# vco-4069-schmitz.net
KiCad netlist of a schematic drawn in EAGLE
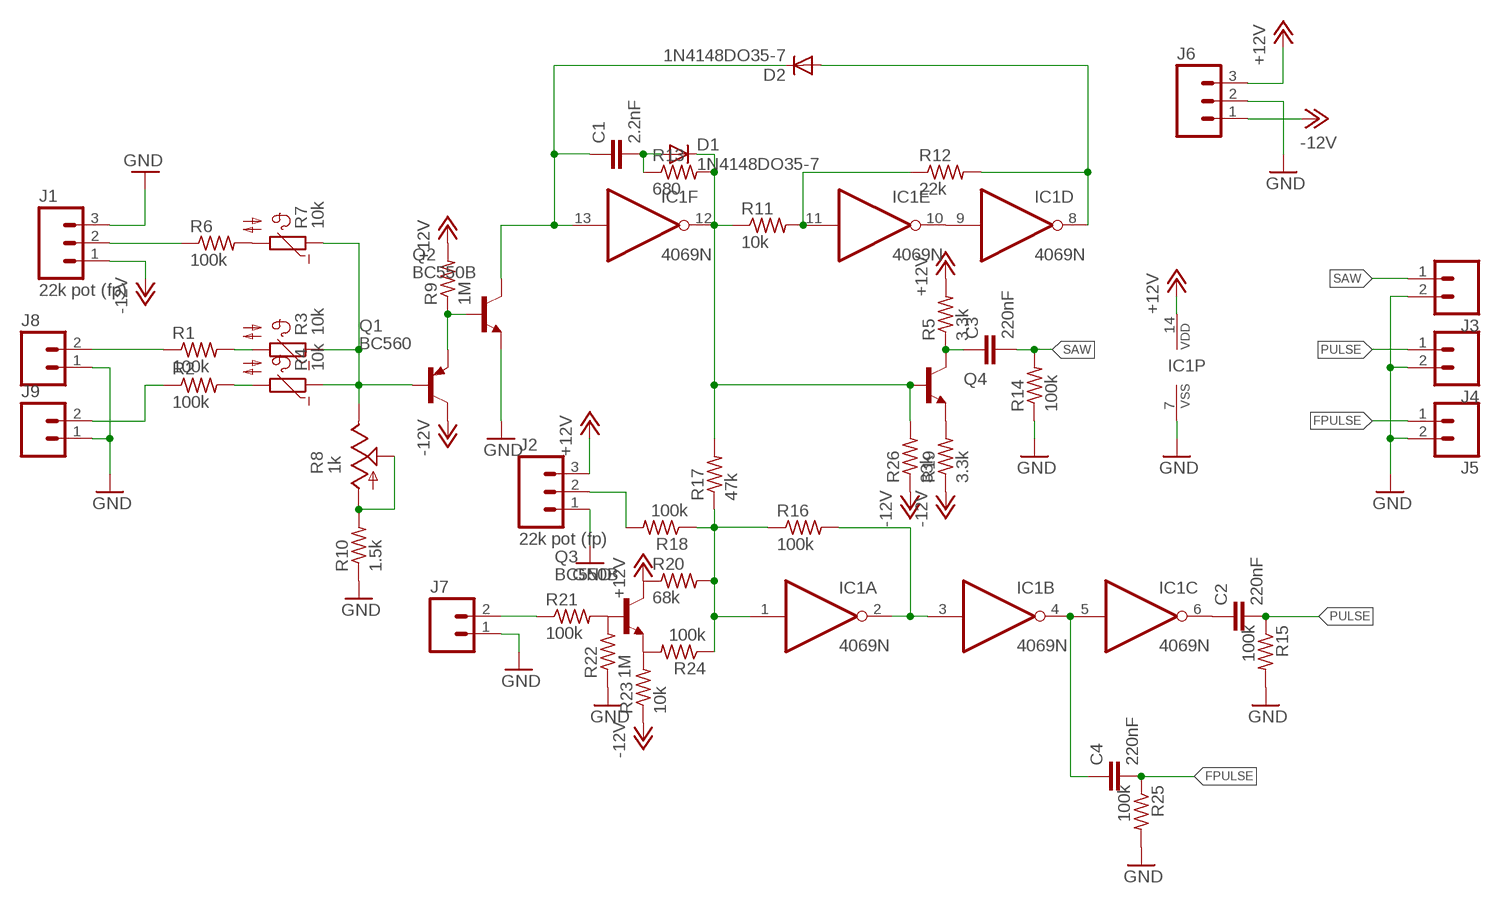
[diagram p0: schematic, sheet 1]

(export (version "E")
  (design (tool "Eeschema 10.0.6"))
  (components
    (comp (ref "C1")
      (value "2.2nF")
      (footprint "eagle-import:C025-025X050")
      (libsource (lib "eagle-import") (part "C-EU025-025X050"))
    )
    (comp (ref "C2")
      (value "220nF")
      (footprint "eagle-import:C025-025X050")
      (libsource (lib "eagle-import") (part "C-EU025-025X050"))
    )
    (comp (ref "C3")
      (value "220nF")
      (footprint "eagle-import:C025-025X050")
      (libsource (lib "eagle-import") (part "C-EU025-025X050"))
    )
    (comp (ref "C4")
      (value "220nF")
      (footprint "eagle-import:C025-025X050")
      (libsource (lib "eagle-import") (part "C-EU025-025X050"))
    )
    (comp (ref "D1")
      (value "1N4148DO35-7")
      (footprint "eagle-import:DO35-7")
      (libsource (lib "eagle-import") (part "1N4148DO35-7"))
    )
    (comp (ref "D2")
      (value "1N4148DO35-7")
      (footprint "eagle-import:DO35-7")
      (libsource (lib "eagle-import") (part "1N4148DO35-7"))
    )
    (comp (ref "IC1")
      (value "4069N")
      (footprint "eagle-import:DIL14")
      (libsource (lib "eagle-import") (part "4069N"))
    )
    (comp (ref "J1")
      (value "22k pot (fp)")
      (footprint "eagle-import:1X03")
      (libsource (lib "eagle-import") (part "M03PTH"))
    )
    (comp (ref "J2")
      (value "22k pot (fp)")
      (footprint "eagle-import:1X03")
      (libsource (lib "eagle-import") (part "M03PTH"))
    )
    (comp (ref "J3")
      (value "M02PTH")
      (footprint "eagle-import:1X02")
      (libsource (lib "eagle-import") (part "M02PTH"))
    )
    (comp (ref "J4")
      (value "M02PTH")
      (footprint "eagle-import:1X02")
      (libsource (lib "eagle-import") (part "M02PTH"))
    )
    (comp (ref "J5")
      (value "M02PTH")
      (footprint "eagle-import:1X02")
      (libsource (lib "eagle-import") (part "M02PTH"))
    )
    (comp (ref "J6")
      (value "M03PTH")
      (footprint "eagle-import:1X03")
      (libsource (lib "eagle-import") (part "M03PTH"))
    )
    (comp (ref "J7")
      (value "M02PTH")
      (footprint "eagle-import:1X02")
      (libsource (lib "eagle-import") (part "M02PTH"))
    )
    (comp (ref "J8")
      (value "M02PTH")
      (footprint "eagle-import:1X02")
      (libsource (lib "eagle-import") (part "M02PTH"))
    )
    (comp (ref "J9")
      (value "M02PTH")
      (footprint "eagle-import:1X02")
      (libsource (lib "eagle-import") (part "M02PTH"))
    )
    (comp (ref "Q1")
      (value "BC560")
      (footprint "eagle-import:TO92-EBC")
      (libsource (lib "eagle-import") (part "BC560"))
    )
    (comp (ref "Q2")
      (value "BC550B")
      (footprint "eagle-import:TO92-EBC")
      (libsource (lib "eagle-import") (part "BC550B"))
    )
    (comp (ref "Q3")
      (value "BC550B")
      (footprint "eagle-import:TO92-EBC")
      (libsource (lib "eagle-import") (part "BC550B"))
    )
    (comp (ref "Q4")
      (value "TRANSISTOR_NPNBC547")
      (footprint "eagle-import:TO-92-AMMO")
      (libsource (lib "eagle-import") (part "TRANSISTOR_NPNBC547"))
    )
    (comp (ref "R1")
      (value "100k")
      (footprint "eagle-import:0207_2V")
      (libsource (lib "eagle-import") (part "R-US_0207/2V"))
    )
    (comp (ref "R2")
      (value "100k")
      (footprint "eagle-import:0207_2V")
      (libsource (lib "eagle-import") (part "R-US_0207/2V"))
    )
    (comp (ref "R3")
      (value "10k")
      (footprint "eagle-import:N640")
      (libsource (lib "eagle-import") (part "NTC640-9"))
    )
    (comp (ref "R4")
      (value "10k")
      (footprint "eagle-import:N640")
      (libsource (lib "eagle-import") (part "NTC640-9"))
    )
    (comp (ref "R5")
      (value "3.3k")
      (footprint "eagle-import:0207_2V")
      (libsource (lib "eagle-import") (part "R-US_0207/2V"))
    )
    (comp (ref "R6")
      (value "100k")
      (footprint "eagle-import:0207_2V")
      (libsource (lib "eagle-import") (part "R-US_0207/2V"))
    )
    (comp (ref "R7")
      (value "10k")
      (footprint "eagle-import:N640")
      (libsource (lib "eagle-import") (part "NTC640-9"))
    )
    (comp (ref "R8")
      (value "1k")
      (footprint "eagle-import:B25P")
      (libsource (lib "eagle-import") (part "TRIM_US-B25P"))
    )
    (comp (ref "R9")
      (value "1M")
      (footprint "eagle-import:0207_2V")
      (libsource (lib "eagle-import") (part "R-US_0207/2V"))
    )
    (comp (ref "R10")
      (value "1.5k")
      (footprint "eagle-import:0207_2V")
      (libsource (lib "eagle-import") (part "R-US_0207/2V"))
    )
    (comp (ref "R11")
      (value "10k")
      (footprint "eagle-import:0207_2V")
      (libsource (lib "eagle-import") (part "R-US_0207/2V"))
    )
    (comp (ref "R12")
      (value "22k")
      (footprint "eagle-import:0207_2V")
      (libsource (lib "eagle-import") (part "R-US_0207/2V"))
    )
    (comp (ref "R13")
      (value "680")
      (footprint "eagle-import:0204_7")
      (libsource (lib "eagle-import") (part "R-US_0204/7"))
    )
    (comp (ref "R14")
      (value "100k")
      (footprint "eagle-import:0207_2V")
      (libsource (lib "eagle-import") (part "R-US_0207/2V"))
    )
    (comp (ref "R15")
      (value "100k")
      (footprint "eagle-import:0207_2V")
      (libsource (lib "eagle-import") (part "R-US_0207/2V"))
    )
    (comp (ref "R16")
      (value "100k")
      (footprint "eagle-import:0207_2V")
      (libsource (lib "eagle-import") (part "R-US_0207/2V"))
    )
    (comp (ref "R17")
      (value "47k")
      (footprint "eagle-import:0207_2V")
      (libsource (lib "eagle-import") (part "R-US_0207/2V"))
    )
    (comp (ref "R18")
      (value "100k")
      (footprint "eagle-import:0207_2V")
      (libsource (lib "eagle-import") (part "R-US_0207/2V"))
    )
    (comp (ref "R19")
      (value "3.3k")
      (footprint "eagle-import:0207_2V")
      (libsource (lib "eagle-import") (part "R-US_0207/2V"))
    )
    (comp (ref "R20")
      (value "68k")
      (footprint "eagle-import:0207_2V")
      (libsource (lib "eagle-import") (part "R-US_0207/2V"))
    )
    (comp (ref "R21")
      (value "100k")
      (footprint "eagle-import:0207_2V")
      (libsource (lib "eagle-import") (part "R-US_0207/2V"))
    )
    (comp (ref "R22")
      (value "1M")
      (footprint "eagle-import:0207_2V")
      (libsource (lib "eagle-import") (part "R-US_0207/2V"))
    )
    (comp (ref "R23")
      (value "10k")
      (footprint "eagle-import:0207_5V")
      (libsource (lib "eagle-import") (part "R-US_0207/5V"))
    )
    (comp (ref "R24")
      (value "100k")
      (footprint "eagle-import:0207_2V")
      (libsource (lib "eagle-import") (part "R-US_0207/2V"))
    )
    (comp (ref "R25")
      (value "100k")
      (footprint "eagle-import:0207_2V")
      (libsource (lib "eagle-import") (part "R-US_0207/2V"))
    )
    (comp (ref "R26")
      (value "33k")
      (footprint "eagle-import:0207_2V")
      (libsource (lib "eagle-import") (part "R-US_0207/2V"))
    )
  )
  (nets
    (net (code "1") (name "+12V") (class "Default")
      (node (ref "IC1") (pin "14") (pinfunction "VDD_14") (pintype "power_in"))
      (node (ref "J2") (pin "3") (pinfunction "3_3") (pintype "passive"))
      (node (ref "J6") (pin "3") (pinfunction "3_3") (pintype "passive"))
      (node (ref "Q3") (pin "C") (pinfunction "C_C") (pintype "passive"))
      (node (ref "R20") (pin "1") (pinfunction "1_1") (pintype "passive"))
      (node (ref "R5") (pin "2") (pinfunction "2_2") (pintype "passive"))
      (node (ref "R9") (pin "2") (pinfunction "2_2") (pintype "passive"))
    )
    (net (code "2") (name "-12V") (class "Default")
      (node (ref "J1") (pin "1") (pinfunction "1_1") (pintype "passive"))
      (node (ref "J6") (pin "1") (pinfunction "1_1") (pintype "passive"))
      (node (ref "Q1") (pin "C") (pinfunction "C_C") (pintype "passive"))
      (node (ref "R19") (pin "1") (pinfunction "1_1") (pintype "passive"))
      (node (ref "R23") (pin "1") (pinfunction "1_1") (pintype "passive"))
      (node (ref "R26") (pin "1") (pinfunction "1_1") (pintype "passive"))
    )
    (net (code "3") (name "FPULSE") (class "Default")
      (node (ref "C4") (pin "2") (pinfunction "2_2") (pintype "passive"))
      (node (ref "J5") (pin "1") (pinfunction "1_1") (pintype "passive"))
      (node (ref "R25") (pin "1") (pinfunction "1_1") (pintype "passive"))
    )
    (net (code "4") (name "GND") (class "Default")
      (node (ref "IC1") (pin "7") (pinfunction "VSS_7") (pintype "power_in"))
      (node (ref "J1") (pin "3") (pinfunction "3_3") (pintype "passive"))
      (node (ref "J2") (pin "1") (pinfunction "1_1") (pintype "passive"))
      (node (ref "J3") (pin "2") (pinfunction "2_2") (pintype "passive"))
      (node (ref "J4") (pin "2") (pinfunction "2_2") (pintype "passive"))
      (node (ref "J5") (pin "2") (pinfunction "2_2") (pintype "passive"))
      (node (ref "J6") (pin "2") (pinfunction "2_2") (pintype "passive"))
      (node (ref "J7") (pin "1") (pinfunction "1_1") (pintype "passive"))
      (node (ref "J8") (pin "1") (pinfunction "1_1") (pintype "passive"))
      (node (ref "J9") (pin "1") (pinfunction "1_1") (pintype "passive"))
      (node (ref "Q2") (pin "E") (pinfunction "E_E") (pintype "passive"))
      (node (ref "R10") (pin "1") (pinfunction "1_1") (pintype "passive"))
      (node (ref "R14") (pin "1") (pinfunction "1_1") (pintype "passive"))
      (node (ref "R15") (pin "2") (pinfunction "2_2") (pintype "passive"))
      (node (ref "R22") (pin "1") (pinfunction "1_1") (pintype "passive"))
      (node (ref "R25") (pin "2") (pinfunction "2_2") (pintype "passive"))
    )
    (net (code "5") (name "Net-(C1-Pad2)") (class "Default")
      (node (ref "C1") (pin "2") (pinfunction "2_2") (pintype "passive"))
      (node (ref "D1") (pin "A") (pinfunction "A_A") (pintype "passive"))
      (node (ref "R13") (pin "1") (pinfunction "1_1") (pintype "passive"))
    )
    (net (code "6") (name "Net-(IC1A-I)") (class "Default")
      (node (ref "IC1") (pin "1") (pinfunction "I_1") (pintype "input"))
      (node (ref "R16") (pin "1") (pinfunction "1_1") (pintype "passive"))
      (node (ref "R17") (pin "1") (pinfunction "1_1") (pintype "passive"))
      (node (ref "R18") (pin "1") (pinfunction "1_1") (pintype "passive"))
      (node (ref "R20") (pin "2") (pinfunction "2_2") (pintype "passive"))
      (node (ref "R24") (pin "1") (pinfunction "1_1") (pintype "passive"))
    )
    (net (code "7") (name "Net-(IC1A-O)") (class "Default")
      (node (ref "IC1") (pin "2") (pinfunction "O_2") (pintype "output"))
      (node (ref "IC1") (pin "3") (pinfunction "I_3") (pintype "input"))
      (node (ref "R16") (pin "2") (pinfunction "2_2") (pintype "passive"))
    )
    (net (code "8") (name "Net-(IC1B-O)") (class "Default")
      (node (ref "C4") (pin "1") (pinfunction "1_1") (pintype "passive"))
      (node (ref "IC1") (pin "4") (pinfunction "O_4") (pintype "output"))
      (node (ref "IC1") (pin "5") (pinfunction "I_5") (pintype "input"))
    )
    (net (code "9") (name "Net-(IC1C-O)") (class "Default")
      (node (ref "C2") (pin "1") (pinfunction "1_1") (pintype "passive"))
      (node (ref "IC1") (pin "6") (pinfunction "O_6") (pintype "output"))
    )
    (net (code "10") (name "Net-(IC1D-I)") (class "Default")
      (node (ref "IC1") (pin "10") (pinfunction "O_10") (pintype "output"))
      (node (ref "IC1") (pin "9") (pinfunction "I_9") (pintype "input"))
    )
    (net (code "11") (name "Net-(IC1D-O)") (class "Default")
      (node (ref "D2") (pin "A") (pinfunction "A_A") (pintype "passive"))
      (node (ref "IC1") (pin "8") (pinfunction "O_8") (pintype "output"))
      (node (ref "R12") (pin "2") (pinfunction "2_2") (pintype "passive"))
    )
    (net (code "12") (name "Net-(IC1E-I)") (class "Default")
      (node (ref "IC1") (pin "11") (pinfunction "I_11") (pintype "input"))
      (node (ref "R11") (pin "2") (pinfunction "2_2") (pintype "passive"))
      (node (ref "R12") (pin "1") (pinfunction "1_1") (pintype "passive"))
    )
    (net (code "13") (name "Net-(IC1F-I)") (class "Default")
      (node (ref "C1") (pin "1") (pinfunction "1_1") (pintype "passive"))
      (node (ref "D2") (pin "C") (pinfunction "C_C") (pintype "passive"))
      (node (ref "IC1") (pin "13") (pinfunction "I_13") (pintype "input"))
      (node (ref "Q2") (pin "C") (pinfunction "C_C") (pintype "passive"))
    )
    (net (code "14") (name "Net-(IC1F-O)") (class "Default")
      (node (ref "D1") (pin "C") (pinfunction "C_C") (pintype "passive"))
      (node (ref "IC1") (pin "12") (pinfunction "O_12") (pintype "output"))
      (node (ref "Q4") (pin "2") (pinfunction "B_2") (pintype "passive"))
      (node (ref "R11") (pin "1") (pinfunction "1_1") (pintype "passive"))
      (node (ref "R13") (pin "2") (pinfunction "2_2") (pintype "passive"))
      (node (ref "R17") (pin "2") (pinfunction "2_2") (pintype "passive"))
      (node (ref "R26") (pin "2") (pinfunction "2_2") (pintype "passive"))
    )
    (net (code "15") (name "Net-(J1-Pad2)") (class "Default")
      (node (ref "J1") (pin "2") (pinfunction "2_2") (pintype "passive"))
      (node (ref "R6") (pin "1") (pinfunction "1_1") (pintype "passive"))
    )
    (net (code "16") (name "Net-(J2-Pad2)") (class "Default")
      (node (ref "J2") (pin "2") (pinfunction "2_2") (pintype "passive"))
      (node (ref "R18") (pin "2") (pinfunction "2_2") (pintype "passive"))
    )
    (net (code "17") (name "Net-(J7-Pad2)") (class "Default")
      (node (ref "J7") (pin "2") (pinfunction "2_2") (pintype "passive"))
      (node (ref "R21") (pin "1") (pinfunction "1_1") (pintype "passive"))
    )
    (net (code "18") (name "Net-(J8-Pad2)") (class "Default")
      (node (ref "J8") (pin "2") (pinfunction "2_2") (pintype "passive"))
      (node (ref "R1") (pin "1") (pinfunction "1_1") (pintype "passive"))
    )
    (net (code "19") (name "Net-(J9-Pad2)") (class "Default")
      (node (ref "J9") (pin "2") (pinfunction "2_2") (pintype "passive"))
      (node (ref "R2") (pin "1") (pinfunction "1_1") (pintype "passive"))
    )
    (net (code "20") (name "Net-(Q1-PadB)") (class "Default")
      (node (ref "Q1") (pin "B") (pinfunction "B_B") (pintype "passive"))
      (node (ref "R3") (pin "1") (pinfunction "1_1") (pintype "passive"))
      (node (ref "R4") (pin "1") (pinfunction "1_1") (pintype "passive"))
      (node (ref "R7") (pin "1") (pinfunction "1_1") (pintype "passive"))
      (node (ref "R8") (pin "E") (pinfunction "E_E") (pintype "passive"))
    )
    (net (code "21") (name "Net-(Q1-PadE)") (class "Default")
      (node (ref "Q1") (pin "E") (pinfunction "E_E") (pintype "passive"))
      (node (ref "Q2") (pin "B") (pinfunction "B_B") (pintype "passive"))
      (node (ref "R9") (pin "1") (pinfunction "1_1") (pintype "passive"))
    )
    (net (code "22") (name "Net-(Q3-PadB)") (class "Default")
      (node (ref "Q3") (pin "B") (pinfunction "B_B") (pintype "passive"))
      (node (ref "R21") (pin "2") (pinfunction "2_2") (pintype "passive"))
      (node (ref "R22") (pin "2") (pinfunction "2_2") (pintype "passive"))
    )
    (net (code "23") (name "Net-(Q3-PadE)") (class "Default")
      (node (ref "Q3") (pin "E") (pinfunction "E_E") (pintype "passive"))
      (node (ref "R23") (pin "2") (pinfunction "2_2") (pintype "passive"))
      (node (ref "R24") (pin "2") (pinfunction "2_2") (pintype "passive"))
    )
    (net (code "24") (name "Net-(Q4-C)") (class "Default")
      (node (ref "C3") (pin "1") (pinfunction "1_1") (pintype "passive"))
      (node (ref "Q4") (pin "1") (pinfunction "C_1") (pintype "passive"))
      (node (ref "R5") (pin "1") (pinfunction "1_1") (pintype "passive"))
    )
    (net (code "25") (name "Net-(Q4-E)") (class "Default")
      (node (ref "Q4") (pin "3") (pinfunction "E_3") (pintype "passive"))
      (node (ref "R19") (pin "2") (pinfunction "2_2") (pintype "passive"))
    )
    (net (code "26") (name "Net-(R1-Pad2)") (class "Default")
      (node (ref "R1") (pin "2") (pinfunction "2_2") (pintype "passive"))
      (node (ref "R3") (pin "2") (pinfunction "2_2") (pintype "passive"))
    )
    (net (code "27") (name "Net-(R2-Pad2)") (class "Default")
      (node (ref "R2") (pin "2") (pinfunction "2_2") (pintype "passive"))
      (node (ref "R4") (pin "2") (pinfunction "2_2") (pintype "passive"))
    )
    (net (code "28") (name "Net-(R6-Pad2)") (class "Default")
      (node (ref "R6") (pin "2") (pinfunction "2_2") (pintype "passive"))
      (node (ref "R7") (pin "2") (pinfunction "2_2") (pintype "passive"))
    )
    (net (code "29") (name "Net-(R10-Pad2)") (class "Default")
      (node (ref "R10") (pin "2") (pinfunction "2_2") (pintype "passive"))
      (node (ref "R8") (pin "A") (pinfunction "A_A") (pintype "passive"))
      (node (ref "R8") (pin "S") (pinfunction "S_S") (pintype "passive"))
    )
    (net (code "30") (name "PULSE") (class "Default")
      (node (ref "C2") (pin "2") (pinfunction "2_2") (pintype "passive"))
      (node (ref "J4") (pin "1") (pinfunction "1_1") (pintype "passive"))
      (node (ref "R15") (pin "1") (pinfunction "1_1") (pintype "passive"))
    )
    (net (code "31") (name "SAW") (class "Default")
      (node (ref "C3") (pin "2") (pinfunction "2_2") (pintype "passive"))
      (node (ref "J3") (pin "1") (pinfunction "1_1") (pintype "passive"))
      (node (ref "R14") (pin "2") (pinfunction "2_2") (pintype "passive"))
    )
  )
)
